# TopSheet.net
KiCad netlist of a schematic drawn in Altium Designer
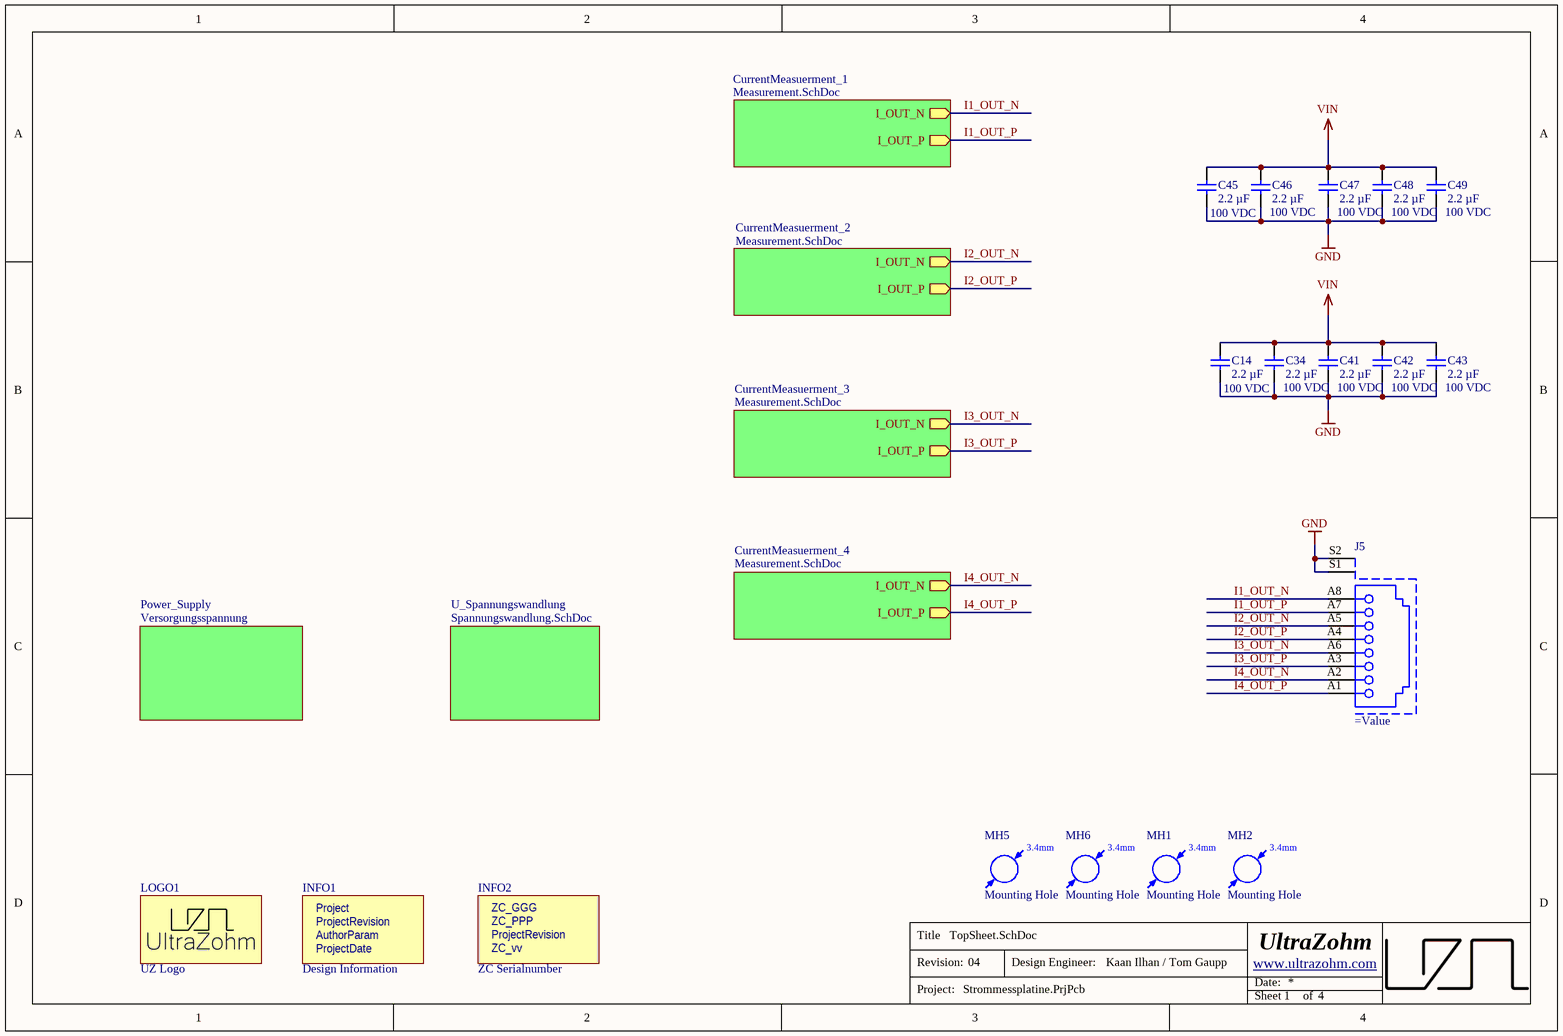
[diagram p0: TopSheet.SchDoc]

(export (version "E")
  (design (tool "Eeschema 10.0.6"))
  (components
    (comp (ref "C14")
      (value "2.2 µF")
      (footprint "C_1210_TE")
      (description "100V 2.2uF X7R ±10% 1210 Multilayer Ceramic Capacitors MLCC - SMD/SMT ROHS")
      (fields
        (field (name "MANUFACTURER PART NUMBER") "FS32X225K101EGG")
        (field (name "MANUFACTURER") "PSA(Prosperity Dielectrics)")
        (field (name "VOLTAGE RATING") "100 VDC")
        (field (name "CREATED FROM") "AGeiger")
      )
      (libsource (lib "user") (part "CAP-NP"))
    )
    (comp (ref "C34")
      (value "2.2 µF")
      (footprint "C_1210_TE")
      (description "100V 2.2uF X7R ±10% 1210 Multilayer Ceramic Capacitors MLCC - SMD/SMT ROHS")
      (fields
        (field (name "MANUFACTURER PART NUMBER") "FS32X225K101EGG")
        (field (name "MANUFACTURER") "PSA(Prosperity Dielectrics)")
        (field (name "VOLTAGE RATING") "100 VDC")
        (field (name "CREATED FROM") "AGeiger")
      )
      (libsource (lib "user") (part "CAP-NP"))
    )
    (comp (ref "C41")
      (value "2.2 µF")
      (footprint "C_1210_TE")
      (description "100V 2.2uF X7R ±10% 1210 Multilayer Ceramic Capacitors MLCC - SMD/SMT ROHS")
      (fields
        (field (name "MANUFACTURER PART NUMBER") "FS32X225K101EGG")
        (field (name "MANUFACTURER") "PSA(Prosperity Dielectrics)")
        (field (name "VOLTAGE RATING") "100 VDC")
        (field (name "CREATED FROM") "AGeiger")
      )
      (libsource (lib "user") (part "CAP-NP"))
    )
    (comp (ref "C42")
      (value "2.2 µF")
      (footprint "C_1210_TE")
      (description "100V 2.2uF X7R ±10% 1210 Multilayer Ceramic Capacitors MLCC - SMD/SMT ROHS")
      (fields
        (field (name "MANUFACTURER PART NUMBER") "FS32X225K101EGG")
        (field (name "MANUFACTURER") "PSA(Prosperity Dielectrics)")
        (field (name "VOLTAGE RATING") "100 VDC")
        (field (name "CREATED FROM") "AGeiger")
      )
      (libsource (lib "user") (part "CAP-NP"))
    )
    (comp (ref "C43")
      (value "2.2 µF")
      (footprint "C_1210_TE")
      (description "100V 2.2uF X7R ±10% 1210 Multilayer Ceramic Capacitors MLCC - SMD/SMT ROHS")
      (fields
        (field (name "MANUFACTURER PART NUMBER") "FS32X225K101EGG")
        (field (name "MANUFACTURER") "PSA(Prosperity Dielectrics)")
        (field (name "VOLTAGE RATING") "100 VDC")
        (field (name "CREATED FROM") "AGeiger")
      )
      (libsource (lib "user") (part "CAP-NP"))
    )
    (comp (ref "C45")
      (value "2.2 µF")
      (footprint "C_1210_TE")
      (description "100V 2.2uF X7R ±10% 1210 Multilayer Ceramic Capacitors MLCC - SMD/SMT ROHS")
      (fields
        (field (name "MANUFACTURER PART NUMBER") "FS32X225K101EGG")
        (field (name "MANUFACTURER") "PSA(Prosperity Dielectrics)")
        (field (name "VOLTAGE RATING") "100 VDC")
        (field (name "CREATED FROM") "AGeiger")
      )
      (libsource (lib "user") (part "CAP-NP"))
    )
    (comp (ref "C46")
      (value "2.2 µF")
      (footprint "C_1210_TE")
      (description "100V 2.2uF X7R ±10% 1210 Multilayer Ceramic Capacitors MLCC - SMD/SMT ROHS")
      (fields
        (field (name "MANUFACTURER PART NUMBER") "FS32X225K101EGG")
        (field (name "MANUFACTURER") "PSA(Prosperity Dielectrics)")
        (field (name "VOLTAGE RATING") "100 VDC")
        (field (name "CREATED FROM") "AGeiger")
      )
      (libsource (lib "user") (part "CAP-NP"))
    )
    (comp (ref "C47")
      (value "2.2 µF")
      (footprint "C_1210_TE")
      (description "100V 2.2uF X7R ±10% 1210 Multilayer Ceramic Capacitors MLCC - SMD/SMT ROHS")
      (fields
        (field (name "MANUFACTURER PART NUMBER") "FS32X225K101EGG")
        (field (name "MANUFACTURER") "PSA(Prosperity Dielectrics)")
        (field (name "VOLTAGE RATING") "100 VDC")
        (field (name "CREATED FROM") "AGeiger")
      )
      (libsource (lib "user") (part "CAP-NP"))
    )
    (comp (ref "C48")
      (value "2.2 µF")
      (footprint "C_1210_TE")
      (description "100V 2.2uF X7R ±10% 1210 Multilayer Ceramic Capacitors MLCC - SMD/SMT ROHS")
      (fields
        (field (name "MANUFACTURER PART NUMBER") "FS32X225K101EGG")
        (field (name "MANUFACTURER") "PSA(Prosperity Dielectrics)")
        (field (name "VOLTAGE RATING") "100 VDC")
        (field (name "CREATED FROM") "AGeiger")
      )
      (libsource (lib "user") (part "CAP-NP"))
    )
    (comp (ref "C49")
      (value "2.2 µF")
      (footprint "C_1210_TE")
      (description "100V 2.2uF X7R ±10% 1210 Multilayer Ceramic Capacitors MLCC - SMD/SMT ROHS")
      (fields
        (field (name "MANUFACTURER PART NUMBER") "FS32X225K101EGG")
        (field (name "MANUFACTURER") "PSA(Prosperity Dielectrics)")
        (field (name "VOLTAGE RATING") "100 VDC")
        (field (name "CREATED FROM") "AGeiger")
      )
      (libsource (lib "user") (part "CAP-NP"))
    )
    (comp (ref "INFO1")
      (value "Design Information")
      (footprint "Design_info")
      (fields (field (name "MANUFACTURER") "UltraZohm") (field (name "CREATED FROM") "MGremer"))
      (libsource (lib "user") (part "Design_info"))
    )
    (comp (ref "INFO2")
      (value "ZC Serialnumber")
      (footprint "ZC-Serial")
      (fields
        (field (name "MANUFACTURER PART NUMBER") "ZC-Serial")
        (field (name "MANUFACTURER") "UltraZohm")
        (field (name "CREATED FROM") "FRosner")
      )
      (libsource (lib "user") (part "ZC_Serial"))
    )
    (comp (ref "J5")
      (value "~")
      (footprint "R-RJ45R10P-B000")
      (fields
        (field (name "MANUFACTURER PART NUMBER") "R-RJ45R10P-B000")
        (field (name "MANUFACTURER") "Ckmtw(Shenzhen Cankemeng)")
        (field (name "LCSC PART NUMBER") "C386758")
        (field (name "CREATED FROM") "KIlhan")
      )
      (libsource (lib "user") (part "R-RJ45R10P-B000"))
    )
    (comp (ref "LOGO1")
      (value "UZ Logo")
      (footprint "UZ_Logo_small")
      (fields
        (field (name "MANUFACTURER PART NUMBER") "Logo small")
        (field (name "MANUFACTURER") "UltraZohm")
        (field (name "CREATED") "Jan2021_Liegmann")
        (field (name "CREATED FROM") "MGremer")
      )
      (libsource (lib "user") (part "UZ Logo"))
    )
    (comp (ref "MH1")
      (value "Mounting Hole")
      (footprint "MH_3.4")
      (fields (field (name "CREATED FROM") "MHlatky"))
      (libsource (lib "user") (part "Mounting Hole"))
    )
    (comp (ref "MH2")
      (value "Mounting Hole")
      (footprint "MH_3.4")
      (fields (field (name "CREATED FROM") "MHlatky"))
      (libsource (lib "user") (part "Mounting Hole"))
    )
    (comp (ref "MH5")
      (value "Mounting Hole")
      (footprint "MH_3.4")
      (fields (field (name "CREATED FROM") "MHlatky"))
      (libsource (lib "user") (part "Mounting Hole"))
    )
    (comp (ref "MH6")
      (value "Mounting Hole")
      (footprint "MH_3.4")
      (fields (field (name "CREATED FROM") "MHlatky"))
      (libsource (lib "user") (part "Mounting Hole"))
    )
  )
  (nets
    (net (code "1") (name "/I1_OUT_N") (class "Default")
      (node (ref "J5") (pin "A8") (pinfunction "A8_A8") (pintype "passive"))
    )
    (net (code "2") (name "/I1_OUT_P") (class "Default")
      (node (ref "J5") (pin "A7") (pinfunction "A7_A7") (pintype "passive"))
    )
    (net (code "3") (name "/I2_OUT_N") (class "Default")
      (node (ref "J5") (pin "A5") (pinfunction "A5_A5") (pintype "passive"))
    )
    (net (code "4") (name "/I2_OUT_P") (class "Default")
      (node (ref "J5") (pin "A4") (pinfunction "A4_A4") (pintype "passive"))
    )
    (net (code "5") (name "/I3_OUT_N") (class "Default")
      (node (ref "J5") (pin "A6") (pinfunction "A6_A6") (pintype "passive"))
    )
    (net (code "6") (name "/I3_OUT_P") (class "Default")
      (node (ref "J5") (pin "A3") (pinfunction "A3_A3") (pintype "passive"))
    )
    (net (code "7") (name "/I4_OUT_N") (class "Default")
      (node (ref "J5") (pin "A2") (pinfunction "A2_A2") (pintype "passive"))
    )
    (net (code "8") (name "/I4_OUT_P") (class "Default")
      (node (ref "J5") (pin "A1") (pinfunction "A1_A1") (pintype "passive"))
    )
    (net (code "9") (name "GND") (class "Default")
      (node (ref "C14") (pin "2") (pinfunction "2_2") (pintype "passive"))
      (node (ref "C34") (pin "2") (pinfunction "2_2") (pintype "passive"))
      (node (ref "C41") (pin "2") (pinfunction "2_2") (pintype "passive"))
      (node (ref "C42") (pin "2") (pinfunction "2_2") (pintype "passive"))
      (node (ref "C43") (pin "2") (pinfunction "2_2") (pintype "passive"))
      (node (ref "C45") (pin "2") (pinfunction "2_2") (pintype "passive"))
      (node (ref "C46") (pin "2") (pinfunction "2_2") (pintype "passive"))
      (node (ref "C47") (pin "2") (pinfunction "2_2") (pintype "passive"))
      (node (ref "C48") (pin "2") (pinfunction "2_2") (pintype "passive"))
      (node (ref "C49") (pin "2") (pinfunction "2_2") (pintype "passive"))
      (node (ref "J5") (pin "S1") (pinfunction "S1_S1") (pintype "passive"))
      (node (ref "J5") (pin "S2") (pinfunction "S2_S2") (pintype "passive"))
    )
    (net (code "10") (name "VIN") (class "Default")
      (node (ref "C14") (pin "1") (pinfunction "1_1") (pintype "passive"))
      (node (ref "C34") (pin "1") (pinfunction "1_1") (pintype "passive"))
      (node (ref "C41") (pin "1") (pinfunction "1_1") (pintype "passive"))
      (node (ref "C42") (pin "1") (pinfunction "1_1") (pintype "passive"))
      (node (ref "C43") (pin "1") (pinfunction "1_1") (pintype "passive"))
      (node (ref "C45") (pin "1") (pinfunction "1_1") (pintype "passive"))
      (node (ref "C46") (pin "1") (pinfunction "1_1") (pintype "passive"))
      (node (ref "C47") (pin "1") (pinfunction "1_1") (pintype "passive"))
      (node (ref "C48") (pin "1") (pinfunction "1_1") (pintype "passive"))
      (node (ref "C49") (pin "1") (pinfunction "1_1") (pintype "passive"))
    )
  )
)
